# Power_PCB.net
KiCad netlist of a schematic drawn in EAGLE
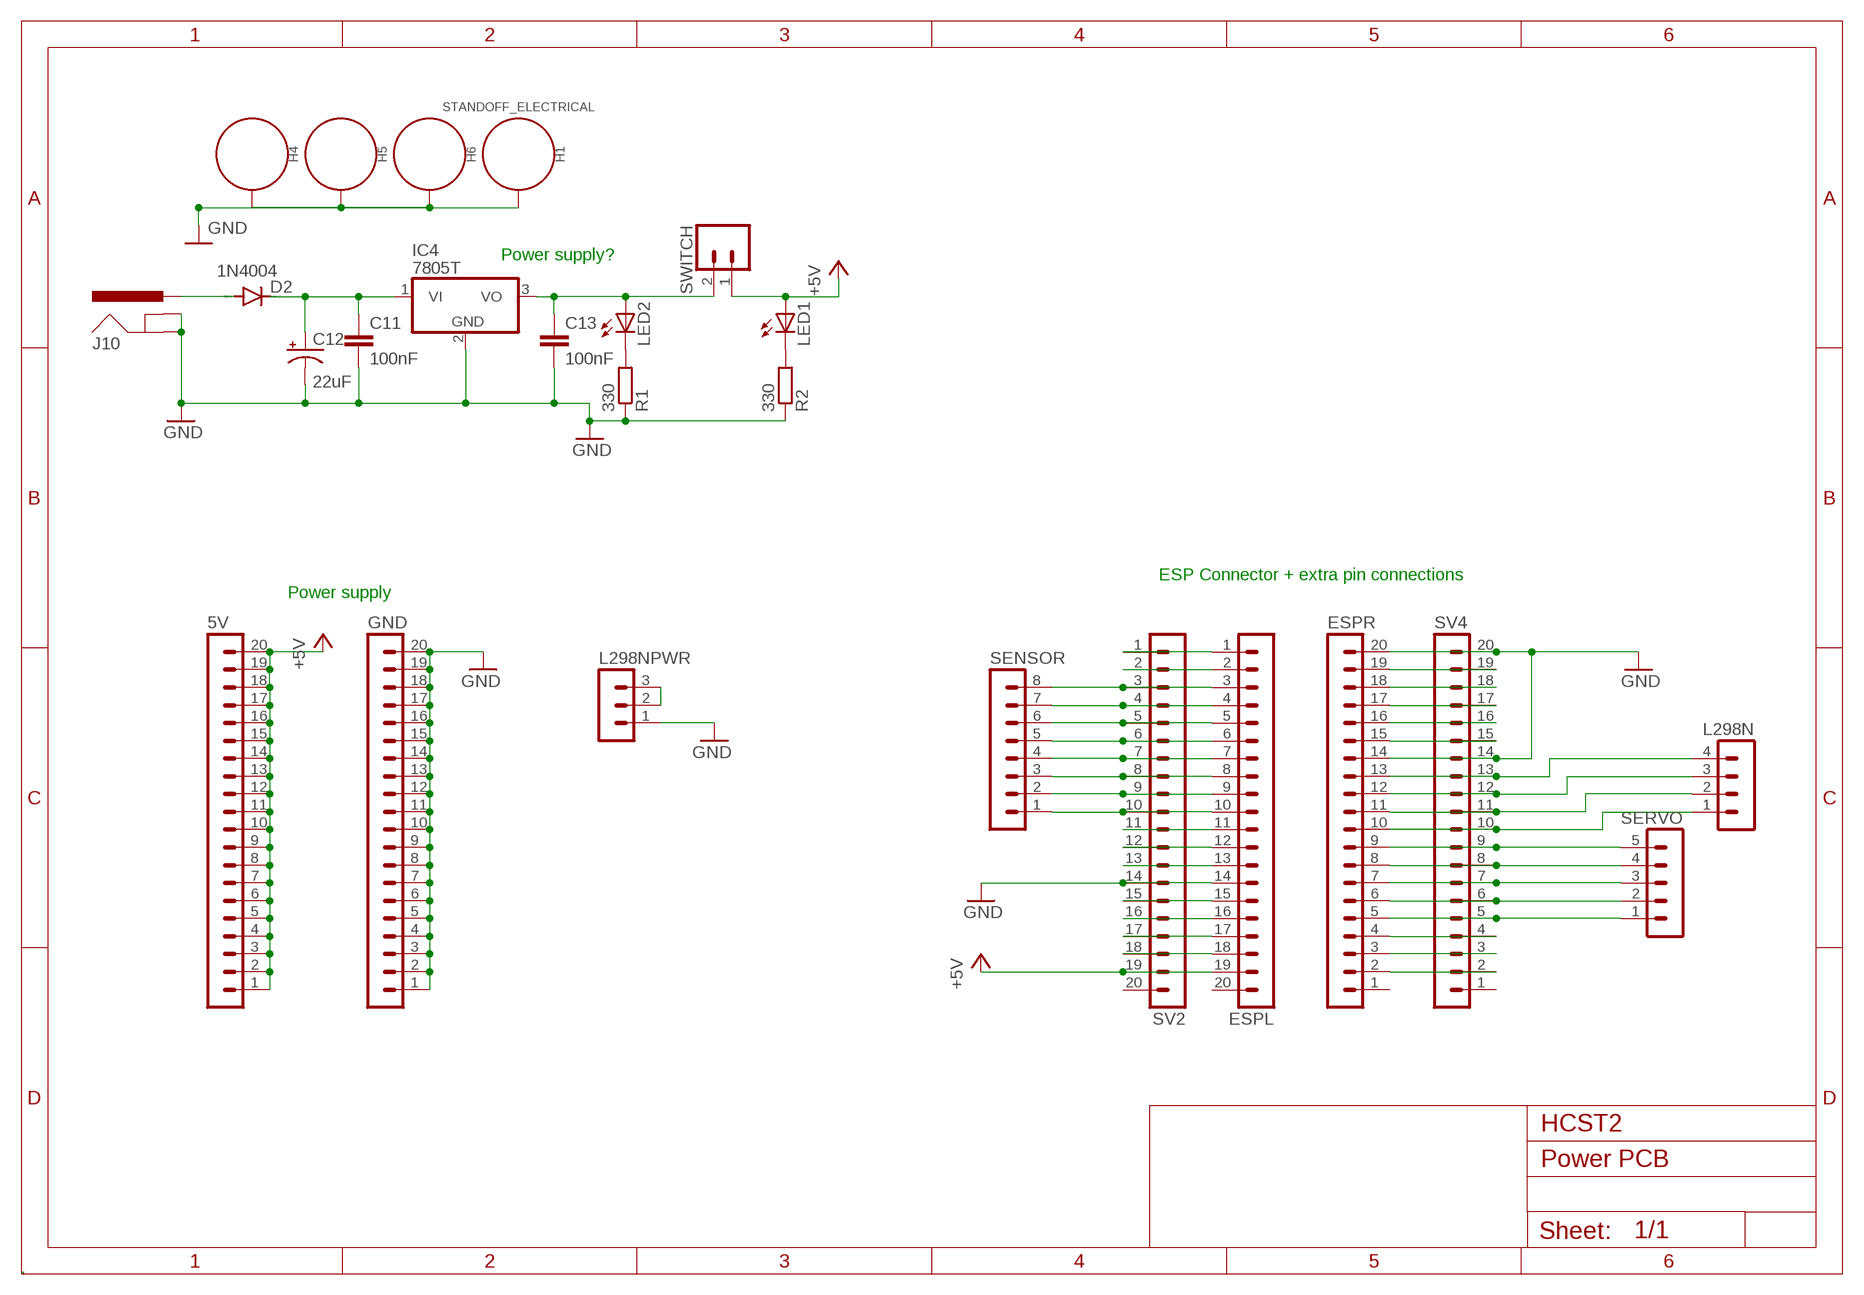
[diagram p0: schematic, sheet 1]

(export (version "E")
  (design (tool "Eeschema 10.0.6"))
  (components
    (comp (ref "5V")
      (value "MA20-1")
      (footprint "eagle-import:MA20-1")
      (libsource (lib "eagle-import") (part "MA20-1"))
    )
    (comp (ref "C11")
      (value "100nF")
      (footprint "eagle-import:C2.5-2")
      (libsource (lib "eagle-import") (part "C2.5/2"))
    )
    (comp (ref "C12")
      (value "22uF")
      (footprint "eagle-import:E2,5-7")
      (libsource (lib "eagle-import") (part "CPOL-USE2.5-7"))
    )
    (comp (ref "C13")
      (value "100nF")
      (footprint "eagle-import:C2.5-2")
      (libsource (lib "eagle-import") (part "C2.5/2"))
    )
    (comp (ref "D2")
      (value "1N4004")
      (footprint "eagle-import:DO41-10")
      (libsource (lib "eagle-import") (part "1N4004"))
    )
    (comp (ref "ESPL")
      (value "MA20-1")
      (footprint "eagle-import:MA20-1")
      (libsource (lib "eagle-import") (part "MA20-1"))
    )
    (comp (ref "ESPR")
      (value "MA20-1")
      (footprint "eagle-import:MA20-1")
      (libsource (lib "eagle-import") (part "MA20-1"))
    )
    (comp (ref "GND")
      (value "MA20-1")
      (footprint "eagle-import:MA20-1")
      (libsource (lib "eagle-import") (part "MA20-1"))
    )
    (comp (ref "H1")
      (value "STANDOFF_ELECTRICAL")
      (footprint "eagle-import:STANDOFF-ELECTRICAL")
      (libsource (lib "eagle-import") (part "STANDOFF_ELECTRICAL"))
    )
    (comp (ref "H4")
      (value "STANDOFF_ELECTRICAL")
      (footprint "eagle-import:STANDOFF-ELECTRICAL")
      (libsource (lib "eagle-import") (part "SparkFun-Hardware_519_STANDOFF_ELECTRICAL"))
    )
    (comp (ref "H5")
      (value "STANDOFF_ELECTRICAL")
      (footprint "eagle-import:STANDOFF-ELECTRICAL")
      (libsource (lib "eagle-import") (part "SparkFun-Hardware_519_STANDOFF_ELECTRICAL"))
    )
    (comp (ref "H6")
      (value "STANDOFF_ELECTRICAL")
      (footprint "eagle-import:STANDOFF-ELECTRICAL")
      (libsource (lib "eagle-import") (part "SparkFun-Hardware_519_STANDOFF_ELECTRICAL"))
    )
    (comp (ref "IC4")
      (value "7805T")
      (footprint "eagle-import:TO220H")
      (libsource (lib "eagle-import") (part "78T05"))
    )
    (comp (ref "J10")
      (value "EL311-ROBOT_SPARKFUN-CONNECTORS_POWER_JACKPTH")
      (footprint "eagle-import:EL311-ROBOT_SPARKFUN-CONNECTORS_POWER_JACK_PTH")
      (libsource (lib "eagle-import") (part "EL311-ROBOT_SPARKFUN-CONNECTORS_POWER_JACKPTH"))
    )
    (comp (ref "L298N")
      (value "MA04-1")
      (footprint "eagle-import:MA04-1")
      (libsource (lib "eagle-import") (part "MA04-1"))
    )
    (comp (ref "L298NPWR")
      (value "MA03-1")
      (footprint "eagle-import:MA03-1")
      (libsource (lib "eagle-import") (part "MA03-1"))
    )
    (comp (ref "LED1")
      (value "LED3MM")
      (footprint "eagle-import:LED3MM")
      (libsource (lib "eagle-import") (part "LED3MM"))
    )
    (comp (ref "LED2")
      (value "LED3MM")
      (footprint "eagle-import:LED3MM")
      (libsource (lib "eagle-import") (part "LED3MM"))
    )
    (comp (ref "R1")
      (value "330")
      (footprint "eagle-import:0207_10")
      (libsource (lib "eagle-import") (part "R-EU_0207/10"))
    )
    (comp (ref "R2")
      (value "330")
      (footprint "eagle-import:0207_10")
      (libsource (lib "eagle-import") (part "R-EU_0207/10"))
    )
    (comp (ref "SENSOR")
      (value "MA08-1")
      (footprint "eagle-import:MA08-1")
      (libsource (lib "eagle-import") (part "MA08-1"))
    )
    (comp (ref "SERVO")
      (value "MA05-1")
      (footprint "eagle-import:MA05-1")
      (libsource (lib "eagle-import") (part "MA05-1"))
    )
    (comp (ref "SV2")
      (value "MA20-1")
      (footprint "eagle-import:MA20-1")
      (libsource (lib "eagle-import") (part "MA20-1"))
    )
    (comp (ref "SV4")
      (value "MA20-1")
      (footprint "eagle-import:MA20-1")
      (libsource (lib "eagle-import") (part "MA20-1"))
    )
    (comp (ref "SWITCH")
      (value "CONN_02")
      (footprint "eagle-import:1X02")
      (libsource (lib "eagle-import") (part "CONN_02"))
    )
  )
  (nets
    (net (code "1") (name "+5V") (class "Default")
      (node (ref "5V") (pin "1") (pinfunction "1_1") (pintype "passive"))
      (node (ref "5V") (pin "10") (pinfunction "10_10") (pintype "passive"))
      (node (ref "5V") (pin "11") (pinfunction "11_11") (pintype "passive"))
      (node (ref "5V") (pin "12") (pinfunction "12_12") (pintype "passive"))
      (node (ref "5V") (pin "13") (pinfunction "13_13") (pintype "passive"))
      (node (ref "5V") (pin "14") (pinfunction "14_14") (pintype "passive"))
      (node (ref "5V") (pin "15") (pinfunction "15_15") (pintype "passive"))
      (node (ref "5V") (pin "16") (pinfunction "16_16") (pintype "passive"))
      (node (ref "5V") (pin "17") (pinfunction "17_17") (pintype "passive"))
      (node (ref "5V") (pin "18") (pinfunction "18_18") (pintype "passive"))
      (node (ref "5V") (pin "19") (pinfunction "19_19") (pintype "passive"))
      (node (ref "5V") (pin "2") (pinfunction "2_2") (pintype "passive"))
      (node (ref "5V") (pin "20") (pinfunction "20_20") (pintype "passive"))
      (node (ref "5V") (pin "3") (pinfunction "3_3") (pintype "passive"))
      (node (ref "5V") (pin "4") (pinfunction "4_4") (pintype "passive"))
      (node (ref "5V") (pin "5") (pinfunction "5_5") (pintype "passive"))
      (node (ref "5V") (pin "6") (pinfunction "6_6") (pintype "passive"))
      (node (ref "5V") (pin "7") (pinfunction "7_7") (pintype "passive"))
      (node (ref "5V") (pin "8") (pinfunction "8_8") (pintype "passive"))
      (node (ref "5V") (pin "9") (pinfunction "9_9") (pintype "passive"))
      (node (ref "ESPL") (pin "19") (pinfunction "19_19") (pintype "passive"))
      (node (ref "LED1") (pin "A") (pinfunction "A_A") (pintype "passive"))
      (node (ref "SV2") (pin "19") (pinfunction "19_19") (pintype "passive"))
      (node (ref "SWITCH") (pin "1") (pinfunction "1_1") (pintype "passive"))
    )
    (net (code "2") (name "GND") (class "Default")
      (node (ref "C11") (pin "2") (pinfunction "2_2") (pintype "passive"))
      (node (ref "C12") (pin "-") (pinfunction "-_-") (pintype "passive"))
      (node (ref "C13") (pin "2") (pinfunction "2_2") (pintype "passive"))
      (node (ref "ESPL") (pin "14") (pinfunction "14_14") (pintype "passive"))
      (node (ref "ESPR") (pin "14") (pinfunction "14_14") (pintype "passive"))
      (node (ref "ESPR") (pin "20") (pinfunction "20_20") (pintype "passive"))
      (node (ref "GND") (pin "1") (pinfunction "1_1") (pintype "passive"))
      (node (ref "GND") (pin "10") (pinfunction "10_10") (pintype "passive"))
      (node (ref "GND") (pin "11") (pinfunction "11_11") (pintype "passive"))
      (node (ref "GND") (pin "12") (pinfunction "12_12") (pintype "passive"))
      (node (ref "GND") (pin "13") (pinfunction "13_13") (pintype "passive"))
      (node (ref "GND") (pin "14") (pinfunction "14_14") (pintype "passive"))
      (node (ref "GND") (pin "15") (pinfunction "15_15") (pintype "passive"))
      (node (ref "GND") (pin "16") (pinfunction "16_16") (pintype "passive"))
      (node (ref "GND") (pin "17") (pinfunction "17_17") (pintype "passive"))
      (node (ref "GND") (pin "18") (pinfunction "18_18") (pintype "passive"))
      (node (ref "GND") (pin "19") (pinfunction "19_19") (pintype "passive"))
      (node (ref "GND") (pin "2") (pinfunction "2_2") (pintype "passive"))
      (node (ref "GND") (pin "20") (pinfunction "20_20") (pintype "passive"))
      (node (ref "GND") (pin "3") (pinfunction "3_3") (pintype "passive"))
      (node (ref "GND") (pin "4") (pinfunction "4_4") (pintype "passive"))
      (node (ref "GND") (pin "5") (pinfunction "5_5") (pintype "passive"))
      (node (ref "GND") (pin "6") (pinfunction "6_6") (pintype "passive"))
      (node (ref "GND") (pin "7") (pinfunction "7_7") (pintype "passive"))
      (node (ref "GND") (pin "8") (pinfunction "8_8") (pintype "passive"))
      (node (ref "GND") (pin "9") (pinfunction "9_9") (pintype "passive"))
      (node (ref "H1") (pin "P1") (pinfunction "P$1_P1") (pintype "bidirectional"))
      (node (ref "H4") (pin "P1") (pinfunction "P$1_P1") (pintype "bidirectional"))
      (node (ref "H5") (pin "P1") (pinfunction "P$1_P1") (pintype "bidirectional"))
      (node (ref "H6") (pin "P1") (pinfunction "P$1_P1") (pintype "bidirectional"))
      (node (ref "IC4") (pin "2") (pinfunction "GND_2") (pintype "passive"))
      (node (ref "J10") (pin "GND") (pinfunction "GND_GND") (pintype "bidirectional"))
      (node (ref "J10") (pin "GNDBREAK") (pinfunction "GNDBREAK_GNDBREAK") (pintype "bidirectional"))
      (node (ref "L298NPWR") (pin "1") (pinfunction "1_1") (pintype "passive"))
      (node (ref "R1") (pin "1") (pinfunction "1_1") (pintype "passive"))
      (node (ref "R2") (pin "1") (pinfunction "1_1") (pintype "passive"))
      (node (ref "SV2") (pin "14") (pinfunction "14_14") (pintype "passive"))
      (node (ref "SV4") (pin "14") (pinfunction "14_14") (pintype "passive"))
      (node (ref "SV4") (pin "20") (pinfunction "20_20") (pintype "passive"))
    )
    (net (code "3") (name "Net-(D2-PadA)") (class "Default")
      (node (ref "D2") (pin "A") (pinfunction "A_A") (pintype "passive"))
      (node (ref "J10") (pin "PWR") (pinfunction "PWR_PWR") (pintype "bidirectional"))
    )
    (net (code "4") (name "Net-(ESPL-Pad1)") (class "Default")
      (node (ref "ESPL") (pin "1") (pinfunction "1_1") (pintype "passive"))
      (node (ref "SV2") (pin "1") (pinfunction "1_1") (pintype "passive"))
    )
    (net (code "5") (name "Net-(ESPL-Pad2)") (class "Default")
      (node (ref "ESPL") (pin "2") (pinfunction "2_2") (pintype "passive"))
      (node (ref "SV2") (pin "2") (pinfunction "2_2") (pintype "passive"))
    )
    (net (code "6") (name "Net-(ESPL-Pad3)") (class "Default")
      (node (ref "ESPL") (pin "3") (pinfunction "3_3") (pintype "passive"))
      (node (ref "SENSOR") (pin "8") (pinfunction "8_8") (pintype "passive"))
      (node (ref "SV2") (pin "3") (pinfunction "3_3") (pintype "passive"))
    )
    (net (code "7") (name "Net-(ESPL-Pad4)") (class "Default")
      (node (ref "ESPL") (pin "4") (pinfunction "4_4") (pintype "passive"))
      (node (ref "SENSOR") (pin "7") (pinfunction "7_7") (pintype "passive"))
      (node (ref "SV2") (pin "4") (pinfunction "4_4") (pintype "passive"))
    )
    (net (code "8") (name "Net-(ESPL-Pad5)") (class "Default")
      (node (ref "ESPL") (pin "5") (pinfunction "5_5") (pintype "passive"))
      (node (ref "SENSOR") (pin "6") (pinfunction "6_6") (pintype "passive"))
      (node (ref "SV2") (pin "5") (pinfunction "5_5") (pintype "passive"))
    )
    (net (code "9") (name "Net-(ESPL-Pad6)") (class "Default")
      (node (ref "ESPL") (pin "6") (pinfunction "6_6") (pintype "passive"))
      (node (ref "SENSOR") (pin "5") (pinfunction "5_5") (pintype "passive"))
      (node (ref "SV2") (pin "6") (pinfunction "6_6") (pintype "passive"))
    )
    (net (code "10") (name "Net-(ESPL-Pad7)") (class "Default")
      (node (ref "ESPL") (pin "7") (pinfunction "7_7") (pintype "passive"))
      (node (ref "SENSOR") (pin "4") (pinfunction "4_4") (pintype "passive"))
      (node (ref "SV2") (pin "7") (pinfunction "7_7") (pintype "passive"))
    )
    (net (code "11") (name "Net-(ESPL-Pad8)") (class "Default")
      (node (ref "ESPL") (pin "8") (pinfunction "8_8") (pintype "passive"))
      (node (ref "SENSOR") (pin "3") (pinfunction "3_3") (pintype "passive"))
      (node (ref "SV2") (pin "8") (pinfunction "8_8") (pintype "passive"))
    )
    (net (code "12") (name "Net-(ESPL-Pad9)") (class "Default")
      (node (ref "ESPL") (pin "9") (pinfunction "9_9") (pintype "passive"))
      (node (ref "SENSOR") (pin "2") (pinfunction "2_2") (pintype "passive"))
      (node (ref "SV2") (pin "9") (pinfunction "9_9") (pintype "passive"))
    )
    (net (code "13") (name "Net-(ESPL-Pad10)") (class "Default")
      (node (ref "ESPL") (pin "10") (pinfunction "10_10") (pintype "passive"))
      (node (ref "SENSOR") (pin "1") (pinfunction "1_1") (pintype "passive"))
      (node (ref "SV2") (pin "10") (pinfunction "10_10") (pintype "passive"))
    )
    (net (code "14") (name "Net-(ESPL-Pad11)") (class "Default")
      (node (ref "ESPL") (pin "11") (pinfunction "11_11") (pintype "passive"))
      (node (ref "SV2") (pin "11") (pinfunction "11_11") (pintype "passive"))
    )
    (net (code "15") (name "Net-(ESPL-Pad12)") (class "Default")
      (node (ref "ESPL") (pin "12") (pinfunction "12_12") (pintype "passive"))
      (node (ref "SV2") (pin "12") (pinfunction "12_12") (pintype "passive"))
    )
    (net (code "16") (name "Net-(ESPL-Pad13)") (class "Default")
      (node (ref "ESPL") (pin "13") (pinfunction "13_13") (pintype "passive"))
      (node (ref "SV2") (pin "13") (pinfunction "13_13") (pintype "passive"))
    )
    (net (code "17") (name "Net-(ESPL-Pad15)") (class "Default")
      (node (ref "ESPL") (pin "15") (pinfunction "15_15") (pintype "passive"))
      (node (ref "SV2") (pin "15") (pinfunction "15_15") (pintype "passive"))
    )
    (net (code "18") (name "Net-(ESPL-Pad16)") (class "Default")
      (node (ref "ESPL") (pin "16") (pinfunction "16_16") (pintype "passive"))
      (node (ref "SV2") (pin "16") (pinfunction "16_16") (pintype "passive"))
    )
    (net (code "19") (name "Net-(ESPL-Pad17)") (class "Default")
      (node (ref "ESPL") (pin "17") (pinfunction "17_17") (pintype "passive"))
      (node (ref "SV2") (pin "17") (pinfunction "17_17") (pintype "passive"))
    )
    (net (code "20") (name "Net-(ESPL-Pad18)") (class "Default")
      (node (ref "ESPL") (pin "18") (pinfunction "18_18") (pintype "passive"))
      (node (ref "SV2") (pin "18") (pinfunction "18_18") (pintype "passive"))
    )
    (net (code "21") (name "Net-(ESPR-Pad2)") (class "Default")
      (node (ref "ESPR") (pin "2") (pinfunction "2_2") (pintype "passive"))
      (node (ref "SV4") (pin "2") (pinfunction "2_2") (pintype "passive"))
    )
    (net (code "22") (name "Net-(ESPR-Pad3)") (class "Default")
      (node (ref "ESPR") (pin "3") (pinfunction "3_3") (pintype "passive"))
      (node (ref "SV4") (pin "3") (pinfunction "3_3") (pintype "passive"))
    )
    (net (code "23") (name "Net-(ESPR-Pad4)") (class "Default")
      (node (ref "ESPR") (pin "4") (pinfunction "4_4") (pintype "passive"))
      (node (ref "SV4") (pin "4") (pinfunction "4_4") (pintype "passive"))
    )
    (net (code "24") (name "Net-(ESPR-Pad5)") (class "Default")
      (node (ref "ESPR") (pin "5") (pinfunction "5_5") (pintype "passive"))
      (node (ref "SERVO") (pin "1") (pinfunction "1_1") (pintype "passive"))
      (node (ref "SV4") (pin "5") (pinfunction "5_5") (pintype "passive"))
    )
    (net (code "25") (name "Net-(ESPR-Pad6)") (class "Default")
      (node (ref "ESPR") (pin "6") (pinfunction "6_6") (pintype "passive"))
      (node (ref "SERVO") (pin "2") (pinfunction "2_2") (pintype "passive"))
      (node (ref "SV4") (pin "6") (pinfunction "6_6") (pintype "passive"))
    )
    (net (code "26") (name "Net-(ESPR-Pad7)") (class "Default")
      (node (ref "ESPR") (pin "7") (pinfunction "7_7") (pintype "passive"))
      (node (ref "SERVO") (pin "3") (pinfunction "3_3") (pintype "passive"))
      (node (ref "SV4") (pin "7") (pinfunction "7_7") (pintype "passive"))
    )
    (net (code "27") (name "Net-(ESPR-Pad8)") (class "Default")
      (node (ref "ESPR") (pin "8") (pinfunction "8_8") (pintype "passive"))
      (node (ref "SERVO") (pin "4") (pinfunction "4_4") (pintype "passive"))
      (node (ref "SV4") (pin "8") (pinfunction "8_8") (pintype "passive"))
    )
    (net (code "28") (name "Net-(ESPR-Pad9)") (class "Default")
      (node (ref "ESPR") (pin "9") (pinfunction "9_9") (pintype "passive"))
      (node (ref "SERVO") (pin "5") (pinfunction "5_5") (pintype "passive"))
      (node (ref "SV4") (pin "9") (pinfunction "9_9") (pintype "passive"))
    )
    (net (code "29") (name "Net-(ESPR-Pad10)") (class "Default")
      (node (ref "ESPR") (pin "10") (pinfunction "10_10") (pintype "passive"))
      (node (ref "L298N") (pin "1") (pinfunction "1_1") (pintype "passive"))
      (node (ref "SV4") (pin "10") (pinfunction "10_10") (pintype "passive"))
    )
    (net (code "30") (name "Net-(ESPR-Pad11)") (class "Default")
      (node (ref "ESPR") (pin "11") (pinfunction "11_11") (pintype "passive"))
      (node (ref "L298N") (pin "2") (pinfunction "2_2") (pintype "passive"))
      (node (ref "SV4") (pin "11") (pinfunction "11_11") (pintype "passive"))
    )
    (net (code "31") (name "Net-(ESPR-Pad12)") (class "Default")
      (node (ref "ESPR") (pin "12") (pinfunction "12_12") (pintype "passive"))
      (node (ref "L298N") (pin "3") (pinfunction "3_3") (pintype "passive"))
      (node (ref "SV4") (pin "12") (pinfunction "12_12") (pintype "passive"))
    )
    (net (code "32") (name "Net-(ESPR-Pad13)") (class "Default")
      (node (ref "ESPR") (pin "13") (pinfunction "13_13") (pintype "passive"))
      (node (ref "L298N") (pin "4") (pinfunction "4_4") (pintype "passive"))
      (node (ref "SV4") (pin "13") (pinfunction "13_13") (pintype "passive"))
    )
    (net (code "33") (name "Net-(ESPR-Pad15)") (class "Default")
      (node (ref "ESPR") (pin "15") (pinfunction "15_15") (pintype "passive"))
      (node (ref "SV4") (pin "15") (pinfunction "15_15") (pintype "passive"))
    )
    (net (code "34") (name "Net-(ESPR-Pad16)") (class "Default")
      (node (ref "ESPR") (pin "16") (pinfunction "16_16") (pintype "passive"))
      (node (ref "SV4") (pin "16") (pinfunction "16_16") (pintype "passive"))
    )
    (net (code "35") (name "Net-(ESPR-Pad17)") (class "Default")
      (node (ref "ESPR") (pin "17") (pinfunction "17_17") (pintype "passive"))
      (node (ref "SV4") (pin "17") (pinfunction "17_17") (pintype "passive"))
    )
    (net (code "36") (name "Net-(ESPR-Pad18)") (class "Default")
      (node (ref "ESPR") (pin "18") (pinfunction "18_18") (pintype "passive"))
      (node (ref "SV4") (pin "18") (pinfunction "18_18") (pintype "passive"))
    )
    (net (code "37") (name "Net-(ESPR-Pad19)") (class "Default")
      (node (ref "ESPR") (pin "19") (pinfunction "19_19") (pintype "passive"))
      (node (ref "SV4") (pin "19") (pinfunction "19_19") (pintype "passive"))
    )
    (net (code "38") (name "Net-(IC4-VI)") (class "Default")
      (node (ref "C11") (pin "1") (pinfunction "1_1") (pintype "passive"))
      (node (ref "C12") (pin "+") (pinfunction "+_+") (pintype "passive"))
      (node (ref "D2") (pin "C") (pinfunction "C_C") (pintype "passive"))
      (node (ref "IC4") (pin "1") (pinfunction "VI_1") (pintype "input"))
    )
    (net (code "39") (name "Net-(IC4-VO)") (class "Default")
      (node (ref "C13") (pin "1") (pinfunction "1_1") (pintype "passive"))
      (node (ref "IC4") (pin "3") (pinfunction "VO_3") (pintype "passive"))
      (node (ref "LED2") (pin "A") (pinfunction "A_A") (pintype "passive"))
      (node (ref "SWITCH") (pin "2") (pinfunction "2_2") (pintype "passive"))
    )
    (net (code "40") (name "Net-(L298NPWR-Pad2)") (class "Default")
      (node (ref "L298NPWR") (pin "2") (pinfunction "2_2") (pintype "passive"))
      (node (ref "L298NPWR") (pin "3") (pinfunction "3_3") (pintype "passive"))
    )
    (net (code "41") (name "Net-(LED1-C)") (class "Default")
      (node (ref "LED1") (pin "K") (pinfunction "C_K") (pintype "passive"))
      (node (ref "R2") (pin "2") (pinfunction "2_2") (pintype "passive"))
    )
    (net (code "42") (name "Net-(LED2-C)") (class "Default")
      (node (ref "LED2") (pin "K") (pinfunction "C_K") (pintype "passive"))
      (node (ref "R1") (pin "2") (pinfunction "2_2") (pintype "passive"))
    )
    (net (code "43") (name "unconnected-(ESPL-Pad20)") (class "Default")
      (node (ref "ESPL") (pin "20") (pinfunction "20_20") (pintype "passive"))
    )
    (net (code "44") (name "unconnected-(ESPR-Pad1)") (class "Default")
      (node (ref "ESPR") (pin "1") (pinfunction "1_1") (pintype "passive"))
    )
    (net (code "45") (name "unconnected-(SV2-Pad20)") (class "Default")
      (node (ref "SV2") (pin "20") (pinfunction "20_20") (pintype "passive"))
    )
    (net (code "46") (name "unconnected-(SV4-Pad1)") (class "Default")
      (node (ref "SV4") (pin "1") (pinfunction "1_1") (pintype "passive"))
    )
  )
)
